# Red_Build_Button_v1_1.net
KiCad netlist of a schematic drawn in EAGLE
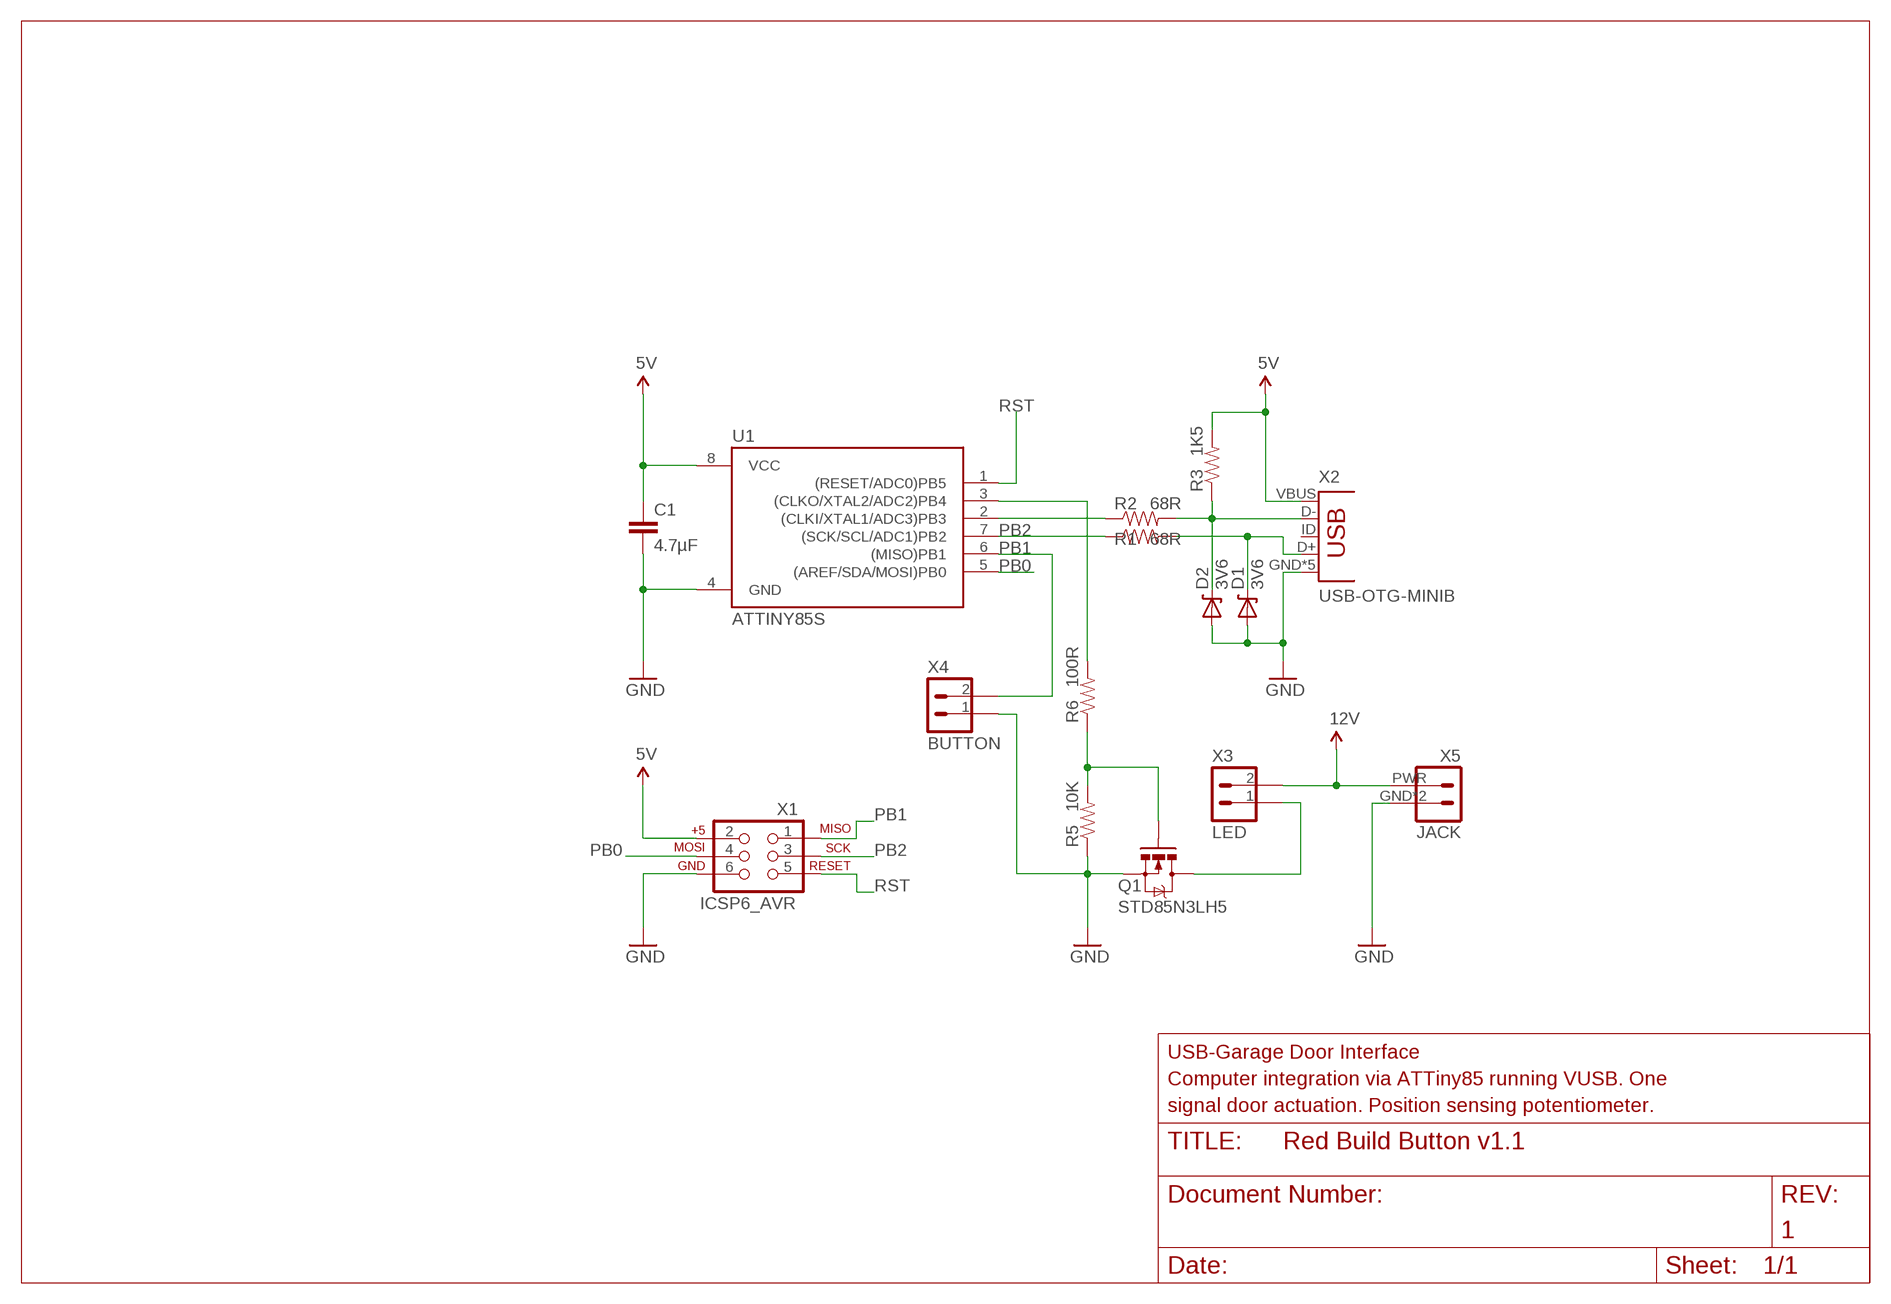
[diagram p0: schematic, sheet 1]

(export (version "E")
  (design (tool "Eeschema 10.0.6"))
  (components
    (comp (ref "C1")
      (value "4.7µF")
      (footprint "eagle-import:0603-CAP")
      (libsource (lib "eagle-import") (part "CAP0603"))
    )
    (comp (ref "D1")
      (value "3V6")
      (footprint "eagle-import:SOD323")
      (libsource (lib "eagle-import") (part "DIODE-ZENERSOD323"))
    )
    (comp (ref "D2")
      (value "3V6")
      (footprint "eagle-import:SOD323")
      (libsource (lib "eagle-import") (part "DIODE-ZENERSOD323"))
    )
    (comp (ref "Q1")
      (value "STD85N3LH5")
      (footprint "eagle-import:DPAK")
      (libsource (lib "eagle-import") (part "MOSFET-NCH-DPAK"))
    )
    (comp (ref "R1")
      (value "68R")
      (footprint "eagle-import:0603-RES")
      (libsource (lib "eagle-import") (part "RESISTOR0603-RES"))
    )
    (comp (ref "R2")
      (value "68R")
      (footprint "eagle-import:0603-RES")
      (libsource (lib "eagle-import") (part "RESISTOR0603-RES"))
    )
    (comp (ref "R3")
      (value "1K5")
      (footprint "eagle-import:0603-RES")
      (libsource (lib "eagle-import") (part "RESISTOR0603-RES"))
    )
    (comp (ref "R5")
      (value "10K")
      (footprint "eagle-import:0603-RES")
      (libsource (lib "eagle-import") (part "RESISTOR0603-RES"))
    )
    (comp (ref "R6")
      (value "100R")
      (footprint "eagle-import:0603-RES")
      (libsource (lib "eagle-import") (part "RESISTOR0603-RES"))
    )
    (comp (ref "U1")
      (value "ATTINY85S")
      (footprint "eagle-import:SOIC8-EIAJ")
      (libsource (lib "eagle-import") (part "ATTINY85S"))
    )
    (comp (ref "X1")
      (value "ICSP6_AVR")
      (footprint "eagle-import:2X3")
      (libsource (lib "eagle-import") (part "ICSP6_AVR"))
    )
    (comp (ref "X2")
      (value "USB-OTG-MINIB")
      (footprint "eagle-import:USB-MINIB-S-SMD")
      (libsource (lib "eagle-import") (part "USB-OTG-MINIB"))
    )
    (comp (ref "X3")
      (value "LED")
      (footprint "eagle-import:JST-XA-S02B")
      (libsource (lib "eagle-import") (part "PWR-SOCKETJST-XA-RTH"))
    )
    (comp (ref "X4")
      (value "BUTTON")
      (footprint "eagle-import:JST-PA-S02B")
      (libsource (lib "eagle-import") (part "PWR-SOCKETJST-PA-RTH"))
    )
    (comp (ref "X5")
      (value "JACK")
      (footprint "eagle-import:PWR-JACK_PTH")
      (libsource (lib "eagle-import") (part "PWR-SOCKETJACK"))
    )
  )
  (nets
    (net (code "1") (name "/PB0") (class "Default")
      (node (ref "U1") (pin "5") (pinfunction "(AREF/SDA/MOSI)PB0_5") (pintype "bidirectional"))
      (node (ref "X1") (pin "4") (pinfunction "MOSI_4") (pintype "passive"))
    )
    (net (code "2") (name "/PB1") (class "Default")
      (node (ref "U1") (pin "6") (pinfunction "(MISO)PB1_6") (pintype "bidirectional"))
      (node (ref "X1") (pin "1") (pinfunction "MISO_1") (pintype "passive"))
      (node (ref "X4") (pin "2") (pinfunction "+_2") (pintype "passive"))
    )
    (net (code "3") (name "/PB2") (class "Default")
      (node (ref "R1") (pin "1") (pinfunction "1_1") (pintype "passive"))
      (node (ref "U1") (pin "7") (pinfunction "(SCK/SCL/ADC1)PB2_7") (pintype "bidirectional"))
      (node (ref "X1") (pin "3") (pinfunction "SCK_3") (pintype "passive"))
    )
    (net (code "4") (name "/RST") (class "Default")
      (node (ref "U1") (pin "1") (pinfunction "(RESET/ADC0)PB5_1") (pintype "bidirectional"))
      (node (ref "X1") (pin "5") (pinfunction "RESET_5") (pintype "passive"))
    )
    (net (code "5") (name "5V") (class "Default")
      (node (ref "C1") (pin "1") (pinfunction "1_1") (pintype "passive"))
      (node (ref "R3") (pin "2") (pinfunction "2_2") (pintype "passive"))
      (node (ref "U1") (pin "8") (pinfunction "VCC_8") (pintype "bidirectional"))
      (node (ref "X1") (pin "2") (pinfunction "5V_2") (pintype "passive"))
      (node (ref "X2") (pin "VBUS") (pinfunction "VBUS_VBUS") (pintype "bidirectional"))
    )
    (net (code "6") (name "12V") (class "Default")
      (node (ref "X3") (pin "2") (pinfunction "+_2") (pintype "passive"))
      (node (ref "X5") (pin "PWR") (pinfunction "+_PWR") (pintype "passive"))
    )
    (net (code "7") (name "GND") (class "Default")
      (node (ref "C1") (pin "2") (pinfunction "2_2") (pintype "passive"))
      (node (ref "D1") (pin "A") (pinfunction "A_A") (pintype "passive"))
      (node (ref "D2") (pin "A") (pinfunction "A_A") (pintype "passive"))
      (node (ref "Q1") (pin "3") (pinfunction "S_3") (pintype "passive"))
      (node (ref "R5") (pin "1") (pinfunction "1_1") (pintype "passive"))
      (node (ref "U1") (pin "4") (pinfunction "GND_4") (pintype "bidirectional"))
      (node (ref "X1") (pin "6") (pinfunction "GND_6") (pintype "passive"))
      (node (ref "X2") (pin "GND") (pinfunction "GND_GND") (pintype "bidirectional"))
      (node (ref "X2") (pin "GND@2") (pinfunction "GND_GND@2") (pintype "bidirectional"))
      (node (ref "X2") (pin "GND@3") (pinfunction "GND_GND@3") (pintype "bidirectional"))
      (node (ref "X2") (pin "GND@4") (pinfunction "GND_GND@4") (pintype "bidirectional"))
      (node (ref "X2") (pin "GND@5") (pinfunction "GND_GND@5") (pintype "bidirectional"))
      (node (ref "X4") (pin "1") (pinfunction "-_1") (pintype "passive"))
      (node (ref "X5") (pin "GND") (pinfunction "-_GND") (pintype "passive"))
      (node (ref "X5") (pin "GND@2") (pinfunction "-_GND@2") (pintype "passive"))
    )
    (net (code "8") (name "Net-(D1-PadC)") (class "Default")
      (node (ref "D1") (pin "C") (pinfunction "C_C") (pintype "passive"))
      (node (ref "R1") (pin "2") (pinfunction "2_2") (pintype "passive"))
      (node (ref "X2") (pin "D+") (pinfunction "D+_D+") (pintype "bidirectional"))
    )
    (net (code "9") (name "Net-(D2-PadC)") (class "Default")
      (node (ref "D2") (pin "C") (pinfunction "C_C") (pintype "passive"))
      (node (ref "R2") (pin "2") (pinfunction "2_2") (pintype "passive"))
      (node (ref "R3") (pin "1") (pinfunction "1_1") (pintype "passive"))
      (node (ref "X2") (pin "D-") (pinfunction "D-_D-") (pintype "bidirectional"))
    )
    (net (code "10") (name "Net-(Q1-D)") (class "Default")
      (node (ref "Q1") (pin "4") (pinfunction "D_4") (pintype "passive"))
      (node (ref "X3") (pin "1") (pinfunction "-_1") (pintype "passive"))
    )
    (net (code "11") (name "Net-(Q1-G)") (class "Default")
      (node (ref "Q1") (pin "1") (pinfunction "G_1") (pintype "passive"))
      (node (ref "R5") (pin "2") (pinfunction "2_2") (pintype "passive"))
      (node (ref "R6") (pin "1") (pinfunction "1_1") (pintype "passive"))
    )
    (net (code "12") (name "Net-(U1-(CLKI{slash}XTAL1{slash}ADC3)PB3)") (class "Default")
      (node (ref "R2") (pin "1") (pinfunction "1_1") (pintype "passive"))
      (node (ref "U1") (pin "2") (pinfunction "(CLKI/XTAL1/ADC3)PB3_2") (pintype "bidirectional"))
    )
    (net (code "13") (name "Net-(U1-(CLKO{slash}XTAL2{slash}ADC2)PB4)") (class "Default")
      (node (ref "R6") (pin "2") (pinfunction "2_2") (pintype "passive"))
      (node (ref "U1") (pin "3") (pinfunction "(CLKO/XTAL2/ADC2)PB4_3") (pintype "bidirectional"))
    )
    (net (code "14") (name "unconnected-(X2-PadID)") (class "Default")
      (node (ref "X2") (pin "ID") (pinfunction "ID_ID") (pintype "bidirectional"))
    )
  )
)
